# top.net
KiCad netlist of a schematic drawn in Altium Designer
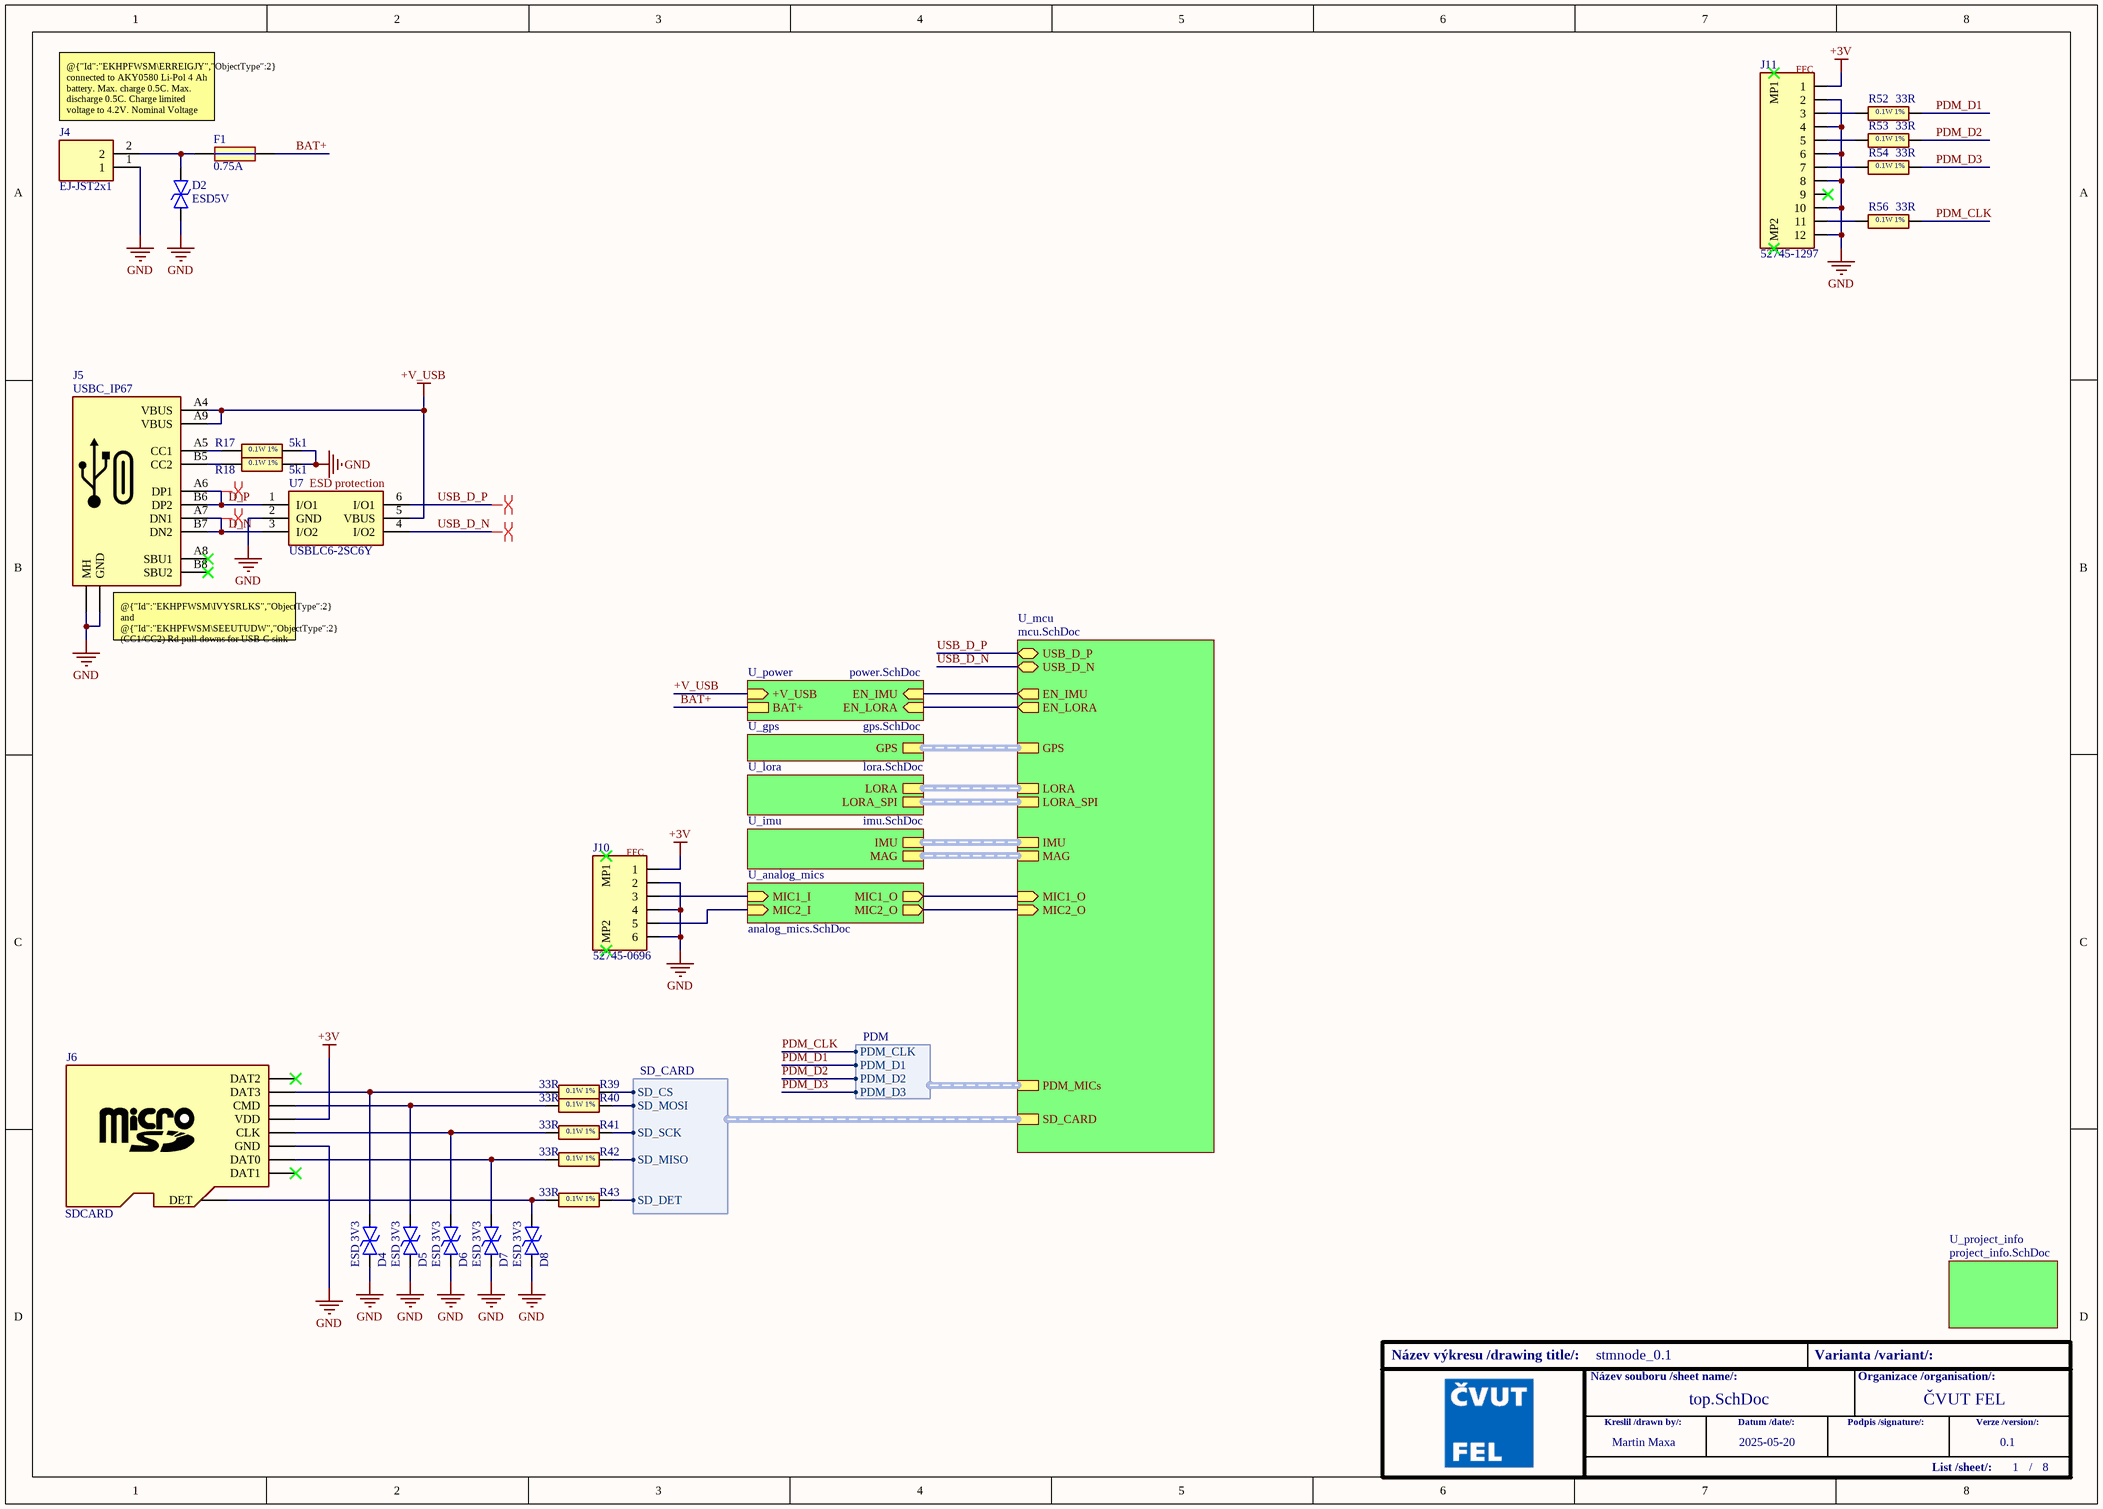
[diagram p0: top.SchDoc]

(export (version "E")
  (design (tool "Eeschema 10.0.6"))
  (components
    (comp (ref "D2")
      (value "ESD5V")
      (footprint "SODFL1006X40N")
      (fields
        (field (name "MANUFACTURER_PART_NUMBER") "D5V0L1B2S9-7")
        (field (name "MOUSER PART NUMBER") "621-D5V0L1B2S9-7")
      )
      (libsource (lib "bch-lib") (part "ED+ESD5V"))
    )
    (comp (ref "D4")
      (value "ESD 3V3")
      (footprint "SODFL1006X40N")
      (fields
        (field (name "MANUFACTURER_PART_NUMBER") "ESD9B3.3ST5G")
        (field (name "MOUSER PART NUMBER") "863-ESD9B3.3ST5G")
      )
      (libsource (lib "bch-lib") (part "ED+ESD3.3V15pF"))
    )
    (comp (ref "D5")
      (value "ESD 3V3")
      (footprint "SODFL1006X40N")
      (fields
        (field (name "MANUFACTURER_PART_NUMBER") "ESD9B3.3ST5G")
        (field (name "MOUSER PART NUMBER") "863-ESD9B3.3ST5G")
      )
      (libsource (lib "bch-lib") (part "ED+ESD3.3V15pF"))
    )
    (comp (ref "D6")
      (value "ESD 3V3")
      (footprint "SODFL1006X40N")
      (fields
        (field (name "MANUFACTURER_PART_NUMBER") "ESD9B3.3ST5G")
        (field (name "MOUSER PART NUMBER") "863-ESD9B3.3ST5G")
      )
      (libsource (lib "bch-lib") (part "ED+ESD3.3V15pF"))
    )
    (comp (ref "D7")
      (value "ESD 3V3")
      (footprint "SODFL1006X40N")
      (fields
        (field (name "MANUFACTURER_PART_NUMBER") "ESD9B3.3ST5G")
        (field (name "MOUSER PART NUMBER") "863-ESD9B3.3ST5G")
      )
      (libsource (lib "bch-lib") (part "ED+ESD3.3V15pF"))
    )
    (comp (ref "D8")
      (value "ESD 3V3")
      (footprint "SODFL1006X40N")
      (fields
        (field (name "MANUFACTURER_PART_NUMBER") "ESD9B3.3ST5G")
        (field (name "MOUSER PART NUMBER") "863-ESD9B3.3ST5G")
      )
      (libsource (lib "bch-lib") (part "ED+ESD3.3V15pF"))
    )
    (comp (ref "F1")
      (value "0.75A")
      (footprint "PTS120630V012")
      (description "Resettable Fuses - PPTC 1206 6V 0.75A 1.1W SMD AEC-Q200 High Temp")
      (fields
        (field (name "MANUFACTURER_PART_NUMBER") "SMDH1206B075TF")
        (field (name "MOUSER PART NUMBER") "603-SMDH1206B075TF")
      )
      (libsource (lib "bch-lib") (part "EF+0.75A6V_1206"))
    )
    (comp (ref "J4")
      (value "EJ-JST2x1")
      (footprint "S2BZRLFSN")
      (description "Konektor: kabel-pl.spoj; zásuvka; vidlice; PIN: 2; PH; 2A; 100V; SMT")
      (fields (field (name "MANUFACTURER_PART_NUMBER") "S2B-ZR (LF)(SN)"))
      (libsource (lib "bch-lib") (part "EJ-JST2x1"))
    )
    (comp (ref "J5")
      (value "USBC_IP67")
      (footprint "USB472003A")
      (description "USB Connectors USB2.0 TypeC Recpt., 3u Gold, 16P Horz Mid Mount SMT, 1.13mm O-set, IP67")
      (fields
        (field (name "MANUFACTURER_PART_NUMBER") "USB4720-03-A")
        (field (name "MOUSER PART NUMBER") "640-USB472003A")
      )
      (libsource (lib "bch-lib") (part "EJ-USBC_IP67"))
    )
    (comp (ref "J6")
      (value "SDCARD")
      (footprint "1051620001")
      (description "Memory Card Connectors Micro SD Push Pull SMT 1.15mm")
      (fields
        (field (name "MANUFACTURER_PART_NUMBER") "105162-0001")
        (field (name "MOUSER PART NUMBER") "538-105162-0001")
      )
      (libsource (lib "bch-lib") (part "EMECH+SDCARD"))
    )
    (comp (ref "J10")
      (value "52745-0696")
      (footprint "527450696")
      (fields (field (name "MOUSER PART NUMBER") "538-52745-0696"))
      (libsource (lib "bch-lib") (part "EJ+52745-0696"))
    )
    (comp (ref "J11")
      (value "52745-1297")
      (footprint "527451297")
      (fields (field (name "MOUSER PART NUMBER") "538-52745-1297"))
      (libsource (lib "bch-lib") (part "EJ+52745-1297"))
    )
    (comp (ref "R17")
      (value "5k1")
      (footprint "RESC1608X55N")
      (description "Thick Film Resistors - SMD 1/10Watt 5.1Kohms 1%")
      (fields
        (field (name "MANUFACTURER_PART_NUMBER") "CRCW06035K10FKEBC")
        (field (name "MOUSER PART NUMBER") "71-CRCW06035K10FKEBC")
      )
      (libsource (lib "bch-lib") (part "ER+5k1"))
    )
    (comp (ref "R18")
      (value "5k1")
      (footprint "RESC1608X55N")
      (description "Thick Film Resistors - SMD 1/10Watt 5.1Kohms 1%")
      (fields
        (field (name "MANUFACTURER_PART_NUMBER") "CRCW06035K10FKEBC")
        (field (name "MOUSER PART NUMBER") "71-CRCW06035K10FKEBC")
      )
      (libsource (lib "bch-lib") (part "ER+5k1"))
    )
    (comp (ref "R39")
      (value "33R")
      (footprint "RESC1608X55N")
      (description "Resistor 1% 0.1W")
      (fields
        (field (name "MANUFACTURER_PART_NUMBER") "0603WAF330JT5E")
        (field (name "MOUSER PART NUMBER") "303-0603WAF330JT5E")
      )
      (libsource (lib "bch-lib") (part "ER+33R"))
    )
    (comp (ref "R40")
      (value "33R")
      (footprint "RESC1608X55N")
      (description "Resistor 1% 0.1W")
      (fields
        (field (name "MANUFACTURER_PART_NUMBER") "0603WAF330JT5E")
        (field (name "MOUSER PART NUMBER") "303-0603WAF330JT5E")
      )
      (libsource (lib "bch-lib") (part "ER+33R"))
    )
    (comp (ref "R41")
      (value "33R")
      (footprint "RESC1608X55N")
      (description "Resistor 1% 0.1W")
      (fields
        (field (name "MANUFACTURER_PART_NUMBER") "0603WAF330JT5E")
        (field (name "MOUSER PART NUMBER") "303-0603WAF330JT5E")
      )
      (libsource (lib "bch-lib") (part "ER+33R"))
    )
    (comp (ref "R42")
      (value "33R")
      (footprint "RESC1608X55N")
      (description "Resistor 1% 0.1W")
      (fields
        (field (name "MANUFACTURER_PART_NUMBER") "0603WAF330JT5E")
        (field (name "MOUSER PART NUMBER") "303-0603WAF330JT5E")
      )
      (libsource (lib "bch-lib") (part "ER+33R"))
    )
    (comp (ref "R43")
      (value "33R")
      (footprint "RESC1608X55N")
      (description "Resistor 1% 0.1W")
      (fields
        (field (name "MANUFACTURER_PART_NUMBER") "0603WAF330JT5E")
        (field (name "MOUSER PART NUMBER") "303-0603WAF330JT5E")
      )
      (libsource (lib "bch-lib") (part "ER+33R"))
    )
    (comp (ref "R52")
      (value "33R")
      (footprint "RESC1608X55N")
      (description "Resistor 1% 0.1W")
      (fields
        (field (name "MANUFACTURER_PART_NUMBER") "0603WAF330JT5E")
        (field (name "MOUSER PART NUMBER") "303-0603WAF330JT5E")
      )
      (libsource (lib "bch-lib") (part "ER+33R"))
    )
    (comp (ref "R53")
      (value "33R")
      (footprint "RESC1608X55N")
      (description "Resistor 1% 0.1W")
      (fields
        (field (name "MANUFACTURER_PART_NUMBER") "0603WAF330JT5E")
        (field (name "MOUSER PART NUMBER") "303-0603WAF330JT5E")
      )
      (libsource (lib "bch-lib") (part "ER+33R"))
    )
    (comp (ref "R54")
      (value "33R")
      (footprint "RESC1608X55N")
      (description "Resistor 1% 0.1W")
      (fields
        (field (name "MANUFACTURER_PART_NUMBER") "0603WAF330JT5E")
        (field (name "MOUSER PART NUMBER") "303-0603WAF330JT5E")
      )
      (libsource (lib "bch-lib") (part "ER+33R"))
    )
    (comp (ref "R56")
      (value "33R")
      (footprint "RESC1608X55N")
      (description "Resistor 1% 0.1W")
      (fields
        (field (name "MANUFACTURER_PART_NUMBER") "0603WAF330JT5E")
        (field (name "MOUSER PART NUMBER") "303-0603WAF330JT5E")
      )
      (libsource (lib "bch-lib") (part "ER+33R"))
    )
    (comp (ref "U7")
      (value "USBLC6-2SC6Y")
      (footprint "SOT95P280X145-6N")
      (fields (field (name "MOUSER PART NUMBER") "511-USBLC6-2SC6Y"))
      (libsource (lib "bch-lib") (part "EU+ESDUSBLC6"))
    )
  )
  (nets
    (net (code "3") (name "+3V") (class "Default")
      (node (ref "J10") (pin "1") (pinfunction "1_1") (pintype "passive"))
      (node (ref "J11") (pin "1") (pinfunction "1_1") (pintype "passive"))
      (node (ref "J6") (pin "4") (pinfunction "VDD_4") (pintype "passive"))
    )
    (net (code "4") (name "+V_USB") (class "Default")
      (node (ref "J5") (pin "A4") (pinfunction "VBUS_A4") (pintype "passive"))
      (node (ref "J5") (pin "A9") (pinfunction "VBUS_A9") (pintype "passive"))
      (node (ref "U7") (pin "5") (pinfunction "VBUS_5") (pintype "passive"))
    )
    (net (code "5") (name "/BAT+") (class "Default")
      (node (ref "F1") (pin "2") (pinfunction "2_2") (pintype "passive"))
    )
    (net (code "6") (name "/D_N") (class "Default")
      (node (ref "J5") (pin "A7") (pinfunction "DN1_A7") (pintype "passive"))
      (node (ref "J5") (pin "B7") (pinfunction "DN2_B7") (pintype "passive"))
      (node (ref "U7") (pin "3") (pinfunction "I/O2_3") (pintype "passive"))
    )
    (net (code "7") (name "/D_P") (class "Default")
      (node (ref "J5") (pin "A6") (pinfunction "DP1_A6") (pintype "passive"))
      (node (ref "J5") (pin "B6") (pinfunction "DP2_B6") (pintype "passive"))
      (node (ref "U7") (pin "1") (pinfunction "I/O1_1") (pintype "passive"))
    )
    (net (code "15") (name "/MIC1_I") (class "Default")
      (node (ref "J10") (pin "3") (pinfunction "3_3") (pintype "passive"))
    )
    (net (code "17") (name "/MIC2_I") (class "Default")
      (node (ref "J10") (pin "5") (pinfunction "5_5") (pintype "passive"))
    )
    (net (code "19") (name "/PDM_CLK") (class "Default")
      (node (ref "R56") (pin "2") (pinfunction "2_2") (pintype "passive"))
    )
    (net (code "20") (name "/PDM_D1") (class "Default")
      (node (ref "R52") (pin "2") (pinfunction "2_2") (pintype "passive"))
    )
    (net (code "21") (name "/PDM_D2") (class "Default")
      (node (ref "R53") (pin "2") (pinfunction "2_2") (pintype "passive"))
    )
    (net (code "22") (name "/PDM_D3") (class "Default")
      (node (ref "R54") (pin "2") (pinfunction "2_2") (pintype "passive"))
    )
    (net (code "23") (name "/SD_CS") (class "Default")
      (node (ref "R39") (pin "2") (pinfunction "2_2") (pintype "passive"))
    )
    (net (code "24") (name "/SD_DET") (class "Default")
      (node (ref "R43") (pin "2") (pinfunction "2_2") (pintype "passive"))
    )
    (net (code "25") (name "/SD_MISO") (class "Default")
      (node (ref "R42") (pin "2") (pinfunction "2_2") (pintype "passive"))
    )
    (net (code "26") (name "/SD_MOSI") (class "Default")
      (node (ref "R40") (pin "2") (pinfunction "2_2") (pintype "passive"))
    )
    (net (code "27") (name "/SD_SCK") (class "Default")
      (node (ref "R41") (pin "2") (pinfunction "2_2") (pintype "passive"))
    )
    (net (code "28") (name "/USB_D_N") (class "Default")
      (node (ref "U7") (pin "4") (pinfunction "I/O2_4") (pintype "passive"))
    )
    (net (code "29") (name "/USB_D_P") (class "Default")
      (node (ref "U7") (pin "6") (pinfunction "I/O1_6") (pintype "passive"))
    )
    (net (code "32") (name "GND") (class "Default")
      (node (ref "D2") (pin "1") (pinfunction "1_1") (pintype "passive"))
      (node (ref "D4") (pin "1") (pinfunction "1_1") (pintype "passive"))
      (node (ref "D5") (pin "1") (pinfunction "1_1") (pintype "passive"))
      (node (ref "D6") (pin "1") (pinfunction "1_1") (pintype "passive"))
      (node (ref "D7") (pin "1") (pinfunction "1_1") (pintype "passive"))
      (node (ref "D8") (pin "1") (pinfunction "1_1") (pintype "passive"))
      (node (ref "J10") (pin "2") (pinfunction "2_2") (pintype "passive"))
      (node (ref "J10") (pin "4") (pinfunction "4_4") (pintype "passive"))
      (node (ref "J10") (pin "6") (pinfunction "6_6") (pintype "passive"))
      (node (ref "J11") (pin "10") (pinfunction "10_10") (pintype "passive"))
      (node (ref "J11") (pin "12") (pinfunction "12_12") (pintype "passive"))
      (node (ref "J11") (pin "2") (pinfunction "2_2") (pintype "passive"))
      (node (ref "J11") (pin "4") (pinfunction "4_4") (pintype "passive"))
      (node (ref "J11") (pin "6") (pinfunction "6_6") (pintype "passive"))
      (node (ref "J11") (pin "8") (pinfunction "8_8") (pintype "passive"))
      (node (ref "J4") (pin "1") (pinfunction "1_1") (pintype "passive"))
      (node (ref "J5") (pin "A12") (pinfunction "GND_A12") (pintype "passive"))
      (node (ref "J5") (pin "MH1") (pinfunction "MH_MH1") (pintype "passive"))
      (node (ref "J6") (pin "10") (pinfunction "GND_10") (pintype "passive"))
      (node (ref "R17") (pin "2") (pinfunction "2_2") (pintype "passive"))
      (node (ref "R18") (pin "2") (pinfunction "2_2") (pintype "passive"))
      (node (ref "U7") (pin "2") (pinfunction "GND_2") (pintype "passive"))
    )
    (net (code "33") (name "Net-(D2-Pad2)") (class "Default")
      (node (ref "D2") (pin "2") (pinfunction "2_2") (pintype "passive"))
      (node (ref "F1") (pin "1") (pinfunction "1_1") (pintype "passive"))
      (node (ref "J4") (pin "2") (pinfunction "2_2") (pintype "passive"))
    )
    (net (code "34") (name "Net-(J5-CC1)") (class "Default")
      (node (ref "J5") (pin "A5") (pinfunction "CC1_A5") (pintype "passive"))
      (node (ref "R17") (pin "1") (pinfunction "1_1") (pintype "passive"))
    )
    (net (code "35") (name "Net-(J5-CC2)") (class "Default")
      (node (ref "J5") (pin "B5") (pinfunction "CC2_B5") (pintype "passive"))
      (node (ref "R18") (pin "1") (pinfunction "1_1") (pintype "passive"))
    )
    (net (code "36") (name "Net-(J6-CLK)") (class "Default")
      (node (ref "D6") (pin "2") (pinfunction "2_2") (pintype "passive"))
      (node (ref "J6") (pin "5") (pinfunction "CLK_5") (pintype "passive"))
      (node (ref "R41") (pin "1") (pinfunction "1_1") (pintype "passive"))
    )
    (net (code "37") (name "Net-(J6-CMD)") (class "Default")
      (node (ref "D5") (pin "2") (pinfunction "2_2") (pintype "passive"))
      (node (ref "J6") (pin "3") (pinfunction "CMD_3") (pintype "passive"))
      (node (ref "R40") (pin "1") (pinfunction "1_1") (pintype "passive"))
    )
    (net (code "38") (name "Net-(J6-DAT0)") (class "Default")
      (node (ref "D7") (pin "2") (pinfunction "2_2") (pintype "passive"))
      (node (ref "J6") (pin "7") (pinfunction "DAT0_7") (pintype "passive"))
      (node (ref "R42") (pin "1") (pinfunction "1_1") (pintype "passive"))
    )
    (net (code "39") (name "Net-(J6-DAT3)") (class "Default")
      (node (ref "D4") (pin "2") (pinfunction "2_2") (pintype "passive"))
      (node (ref "J6") (pin "2") (pinfunction "DAT3_2") (pintype "passive"))
      (node (ref "R39") (pin "1") (pinfunction "1_1") (pintype "passive"))
    )
    (net (code "40") (name "Net-(J6-DET)") (class "Default")
      (node (ref "D8") (pin "2") (pinfunction "2_2") (pintype "passive"))
      (node (ref "J6") (pin "9") (pinfunction "DET_9") (pintype "passive"))
      (node (ref "R43") (pin "1") (pinfunction "1_1") (pintype "passive"))
    )
    (net (code "41") (name "Net-(J11-Pad3)") (class "Default")
      (node (ref "J11") (pin "3") (pinfunction "3_3") (pintype "passive"))
      (node (ref "R52") (pin "1") (pinfunction "1_1") (pintype "passive"))
    )
    (net (code "42") (name "Net-(J11-Pad5)") (class "Default")
      (node (ref "J11") (pin "5") (pinfunction "5_5") (pintype "passive"))
      (node (ref "R53") (pin "1") (pinfunction "1_1") (pintype "passive"))
    )
    (net (code "43") (name "Net-(J11-Pad7)") (class "Default")
      (node (ref "J11") (pin "7") (pinfunction "7_7") (pintype "passive"))
      (node (ref "R54") (pin "1") (pinfunction "1_1") (pintype "passive"))
    )
    (net (code "44") (name "Net-(J11-Pad11)") (class "Default")
      (node (ref "J11") (pin "11") (pinfunction "11_11") (pintype "passive"))
      (node (ref "R56") (pin "1") (pinfunction "1_1") (pintype "passive"))
    )
    (net (code "45") (name "unconnected-(J5-SBU1-PadA8)") (class "Default")
      (node (ref "J5") (pin "A8") (pinfunction "SBU1_A8") (pintype "passive+no_connect"))
    )
    (net (code "46") (name "unconnected-(J5-SBU2-PadB8)") (class "Default")
      (node (ref "J5") (pin "B8") (pinfunction "SBU2_B8") (pintype "passive+no_connect"))
    )
    (net (code "47") (name "unconnected-(J6-DAT1-Pad8)") (class "Default")
      (node (ref "J6") (pin "8") (pinfunction "DAT1_8") (pintype "passive+no_connect"))
    )
    (net (code "48") (name "unconnected-(J6-DAT2-Pad1)") (class "Default")
      (node (ref "J6") (pin "1") (pinfunction "DAT2_1") (pintype "passive+no_connect"))
    )
    (net (code "49") (name "unconnected-(J10-MP1-Pad7)") (class "Default")
      (node (ref "J10") (pin "7") (pinfunction "MP1_7") (pintype "passive+no_connect"))
    )
    (net (code "50") (name "unconnected-(J10-MP2-Pad8)") (class "Default")
      (node (ref "J10") (pin "8") (pinfunction "MP2_8") (pintype "passive+no_connect"))
    )
    (net (code "51") (name "unconnected-(J11-Pad9)") (class "Default")
      (node (ref "J11") (pin "9") (pinfunction "9_9") (pintype "passive+no_connect"))
    )
    (net (code "52") (name "unconnected-(J11-PadMP1)") (class "Default")
      (node (ref "J11") (pin "MP1") (pinfunction "MP1_MP1") (pintype "passive+no_connect"))
    )
    (net (code "53") (name "unconnected-(J11-PadMP2)") (class "Default")
      (node (ref "J11") (pin "MP2") (pinfunction "MP2_MP2") (pintype "passive+no_connect"))
    )
  )
)
